# uio_l.net
KiCad netlist of a schematic drawn in EAGLE
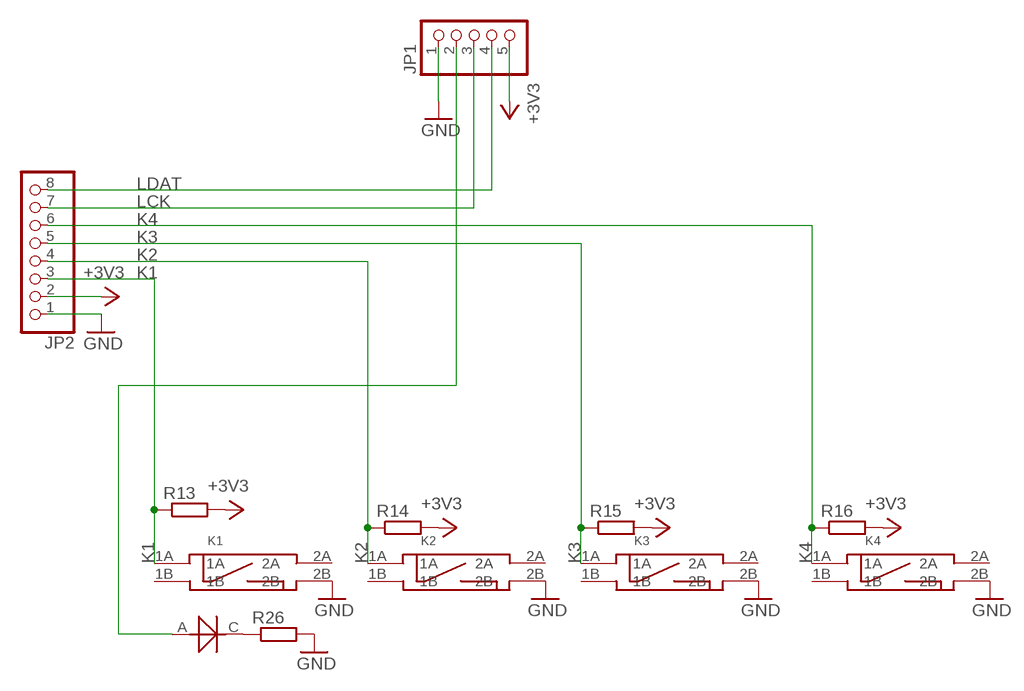
[diagram p0: schematic, sheet 1]

(export (version "E")
  (design (tool "Eeschema 10.0.6"))
  (components
    (comp (ref "JP1")
      (value "PINHD-1X05_2.54-S")
      (footprint "eagle-import:1X05-S")
      (libsource (lib "eagle-import") (part "PINHD-1X05_2.54-S"))
    )
    (comp (ref "JP2")
      (value "PINHD-1X08_2.54-S")
      (footprint "eagle-import:1X08-S")
      (libsource (lib "eagle-import") (part "PINHD-1X08_2.54-S"))
    )
    (comp (ref "K1")
      (value "SWITCH_BD_B")
      (footprint "eagle-import:SW_SMD2")
      (libsource (lib "eagle-import") (part "SWITCH_BD_B"))
    )
    (comp (ref "K2")
      (value "SWITCH_BD_B")
      (footprint "eagle-import:SW_SMD2")
      (libsource (lib "eagle-import") (part "SWITCH_BD_B"))
    )
    (comp (ref "K3")
      (value "SWITCH_BD_B")
      (footprint "eagle-import:SW_SMD2")
      (libsource (lib "eagle-import") (part "SWITCH_BD_B"))
    )
    (comp (ref "K4")
      (value "SWITCH_BD_B")
      (footprint "eagle-import:SW_SMD2")
      (libsource (lib "eagle-import") (part "SWITCH_BD_B"))
    )
    (comp (ref "R13")
      (value "R_0805")
      (footprint "eagle-import:R0805")
      (libsource (lib "eagle-import") (part "R_0805"))
    )
    (comp (ref "R14")
      (value "R_0805")
      (footprint "eagle-import:R0805")
      (libsource (lib "eagle-import") (part "R_0805"))
    )
    (comp (ref "R15")
      (value "R_0805")
      (footprint "eagle-import:R0805")
      (libsource (lib "eagle-import") (part "R_0805"))
    )
    (comp (ref "R16")
      (value "R_0805")
      (footprint "eagle-import:R0805")
      (libsource (lib "eagle-import") (part "R_0805"))
    )
    (comp (ref "R26")
      (value "R_0805")
      (footprint "eagle-import:R0805")
      (libsource (lib "eagle-import") (part "R_0805"))
    )
    (comp (ref "U$14")
      (value "LED5X2")
      (footprint "eagle-import:LED_5X2")
      (libsource (lib "eagle-import") (part "LED5X2"))
    )
  )
  (nets
    (net (code "1") (name "+3V3") (class "Default")
      (node (ref "JP1") (pin "5") (pinfunction "5_5") (pintype "passive"))
      (node (ref "JP2") (pin "2") (pinfunction "2_2") (pintype "passive"))
      (node (ref "R13") (pin "2") (pinfunction "2_2") (pintype "passive"))
      (node (ref "R14") (pin "2") (pinfunction "2_2") (pintype "passive"))
      (node (ref "R15") (pin "2") (pinfunction "2_2") (pintype "passive"))
      (node (ref "R16") (pin "2") (pinfunction "2_2") (pintype "passive"))
    )
    (net (code "2") (name "/K1") (class "Default")
      (node (ref "JP2") (pin "3") (pinfunction "3_3") (pintype "passive"))
      (node (ref "K1") (pin "1A") (pinfunction "1A_1A") (pintype "bidirectional"))
      (node (ref "R13") (pin "1") (pinfunction "1_1") (pintype "passive"))
    )
    (net (code "3") (name "/K2") (class "Default")
      (node (ref "JP2") (pin "4") (pinfunction "4_4") (pintype "passive"))
      (node (ref "K2") (pin "1A") (pinfunction "1A_1A") (pintype "bidirectional"))
      (node (ref "R14") (pin "1") (pinfunction "1_1") (pintype "passive"))
    )
    (net (code "4") (name "/K3") (class "Default")
      (node (ref "JP2") (pin "5") (pinfunction "5_5") (pintype "passive"))
      (node (ref "K3") (pin "1A") (pinfunction "1A_1A") (pintype "bidirectional"))
      (node (ref "R15") (pin "1") (pinfunction "1_1") (pintype "passive"))
    )
    (net (code "5") (name "/K4") (class "Default")
      (node (ref "JP2") (pin "6") (pinfunction "6_6") (pintype "passive"))
      (node (ref "K4") (pin "1A") (pinfunction "1A_1A") (pintype "bidirectional"))
      (node (ref "R16") (pin "1") (pinfunction "1_1") (pintype "passive"))
    )
    (net (code "6") (name "/LCK") (class "Default")
      (node (ref "JP1") (pin "3") (pinfunction "3_3") (pintype "passive"))
      (node (ref "JP2") (pin "7") (pinfunction "7_7") (pintype "passive"))
    )
    (net (code "7") (name "/LDAT") (class "Default")
      (node (ref "JP1") (pin "4") (pinfunction "4_4") (pintype "passive"))
      (node (ref "JP2") (pin "8") (pinfunction "8_8") (pintype "passive"))
    )
    (net (code "8") (name "GND") (class "Default")
      (node (ref "JP1") (pin "1") (pinfunction "1_1") (pintype "passive"))
      (node (ref "JP2") (pin "1") (pinfunction "1_1") (pintype "passive"))
      (node (ref "K1") (pin "2B") (pinfunction "2B_2B") (pintype "bidirectional"))
      (node (ref "K2") (pin "2B") (pinfunction "2B_2B") (pintype "bidirectional"))
      (node (ref "K3") (pin "2B") (pinfunction "2B_2B") (pintype "bidirectional"))
      (node (ref "K4") (pin "2B") (pinfunction "2B_2B") (pintype "bidirectional"))
      (node (ref "R26") (pin "2") (pinfunction "2_2") (pintype "passive"))
    )
    (net (code "9") (name "Net-(JP1-Pad2)") (class "Default")
      (node (ref "JP1") (pin "2") (pinfunction "2_2") (pintype "passive"))
      (node (ref "U$14") (pin "A") (pinfunction "A_A") (pintype "bidirectional"))
    )
    (net (code "10") (name "Net-(R26-Pad1)") (class "Default")
      (node (ref "R26") (pin "1") (pinfunction "1_1") (pintype "passive"))
      (node (ref "U$14") (pin "C") (pinfunction "C_C") (pintype "bidirectional"))
    )
    (net (code "11") (name "unconnected-(K1-Pad1B)") (class "Default")
      (node (ref "K1") (pin "1B") (pinfunction "1B_1B") (pintype "bidirectional"))
    )
    (net (code "12") (name "unconnected-(K1-Pad2A)") (class "Default")
      (node (ref "K1") (pin "2A") (pinfunction "2A_2A") (pintype "bidirectional"))
    )
    (net (code "13") (name "unconnected-(K2-Pad1B)") (class "Default")
      (node (ref "K2") (pin "1B") (pinfunction "1B_1B") (pintype "bidirectional"))
    )
    (net (code "14") (name "unconnected-(K2-Pad2A)") (class "Default")
      (node (ref "K2") (pin "2A") (pinfunction "2A_2A") (pintype "bidirectional"))
    )
    (net (code "15") (name "unconnected-(K3-Pad1B)") (class "Default")
      (node (ref "K3") (pin "1B") (pinfunction "1B_1B") (pintype "bidirectional"))
    )
    (net (code "16") (name "unconnected-(K3-Pad2A)") (class "Default")
      (node (ref "K3") (pin "2A") (pinfunction "2A_2A") (pintype "bidirectional"))
    )
    (net (code "17") (name "unconnected-(K4-Pad1B)") (class "Default")
      (node (ref "K4") (pin "1B") (pinfunction "1B_1B") (pintype "bidirectional"))
    )
    (net (code "18") (name "unconnected-(K4-Pad2A)") (class "Default")
      (node (ref "K4") (pin "2A") (pinfunction "2A_2A") (pintype "bidirectional"))
    )
  )
)
